# regulador_potencia_2.net
KiCad netlist of a schematic drawn in EAGLE
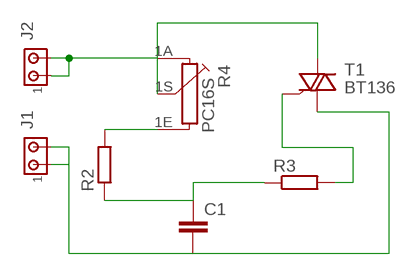
[diagram p0: schematic, sheet 1]

(export (version "E")
  (design (tool "Eeschema 10.0.6"))
  (components
    (comp (ref "C1")
      (value "C2.5/5")
      (footprint "eagle-import:C2.5-5")
      (libsource (lib "eagle-import") (part "C2.5/5"))
    )
    (comp (ref "J1")
      (value "MTA02-156")
      (footprint "eagle-import:1X2MTA")
      (libsource (lib "eagle-import") (part "MTA02-156"))
    )
    (comp (ref "J2")
      (value "MTA02-156")
      (footprint "eagle-import:1X2MTA")
      (libsource (lib "eagle-import") (part "MTA02-156"))
    )
    (comp (ref "R2")
      (value "R-EU_0207/12")
      (footprint "eagle-import:0207_12")
      (libsource (lib "eagle-import") (part "R-EU_0207/12"))
    )
    (comp (ref "R3")
      (value "R-EU_0207/12")
      (footprint "eagle-import:0207_12")
      (libsource (lib "eagle-import") (part "R-EU_0207/12"))
    )
    (comp (ref "R4")
      (value "PC16S")
      (footprint "eagle-import:PC16S")
      (libsource (lib "eagle-import") (part "PC16S"))
    )
    (comp (ref "T1")
      (value "BT136")
      (footprint "eagle-import:TO220AB")
      (libsource (lib "eagle-import") (part "BT136"))
    )
  )
  (nets
    (net (code "1") (name "Net-(C1-Pad1)") (class "Default")
      (node (ref "C1") (pin "1") (pinfunction "1_1") (pintype "passive"))
      (node (ref "R2") (pin "1") (pinfunction "1_1") (pintype "passive"))
      (node (ref "R3") (pin "1") (pinfunction "1_1") (pintype "passive"))
    )
    (net (code "2") (name "Net-(R2-Pad2)") (class "Default")
      (node (ref "R2") (pin "2") (pinfunction "2_2") (pintype "passive"))
      (node (ref "R4") (pin "1E") (pinfunction "1E_1E") (pintype "passive"))
    )
    (net (code "3") (name "Net-(T1-A1)") (class "Default")
      (node (ref "C1") (pin "2") (pinfunction "2_2") (pintype "passive"))
      (node (ref "J1") (pin "1") (pinfunction "1_1") (pintype "passive"))
      (node (ref "J1") (pin "2") (pinfunction "2_2") (pintype "passive"))
      (node (ref "T1") (pin "1") (pinfunction "A1_1") (pintype "passive"))
    )
    (net (code "4") (name "Net-(T1-A2)") (class "Default")
      (node (ref "J2") (pin "1") (pinfunction "1_1") (pintype "passive"))
      (node (ref "J2") (pin "2") (pinfunction "2_2") (pintype "passive"))
      (node (ref "R4") (pin "1A") (pinfunction "1A_1A") (pintype "passive"))
      (node (ref "R4") (pin "1S") (pinfunction "1S_1S") (pintype "passive"))
      (node (ref "T1") (pin "2") (pinfunction "A2_2") (pintype "passive"))
    )
    (net (code "5") (name "Net-(T1-G)") (class "Default")
      (node (ref "R3") (pin "2") (pinfunction "2_2") (pintype "passive"))
      (node (ref "T1") (pin "3") (pinfunction "G_3") (pintype "passive"))
    )
  )
)
